# tumkibot1_relay_module.net
KiCad netlist of a schematic drawn in EasyEDA Pro
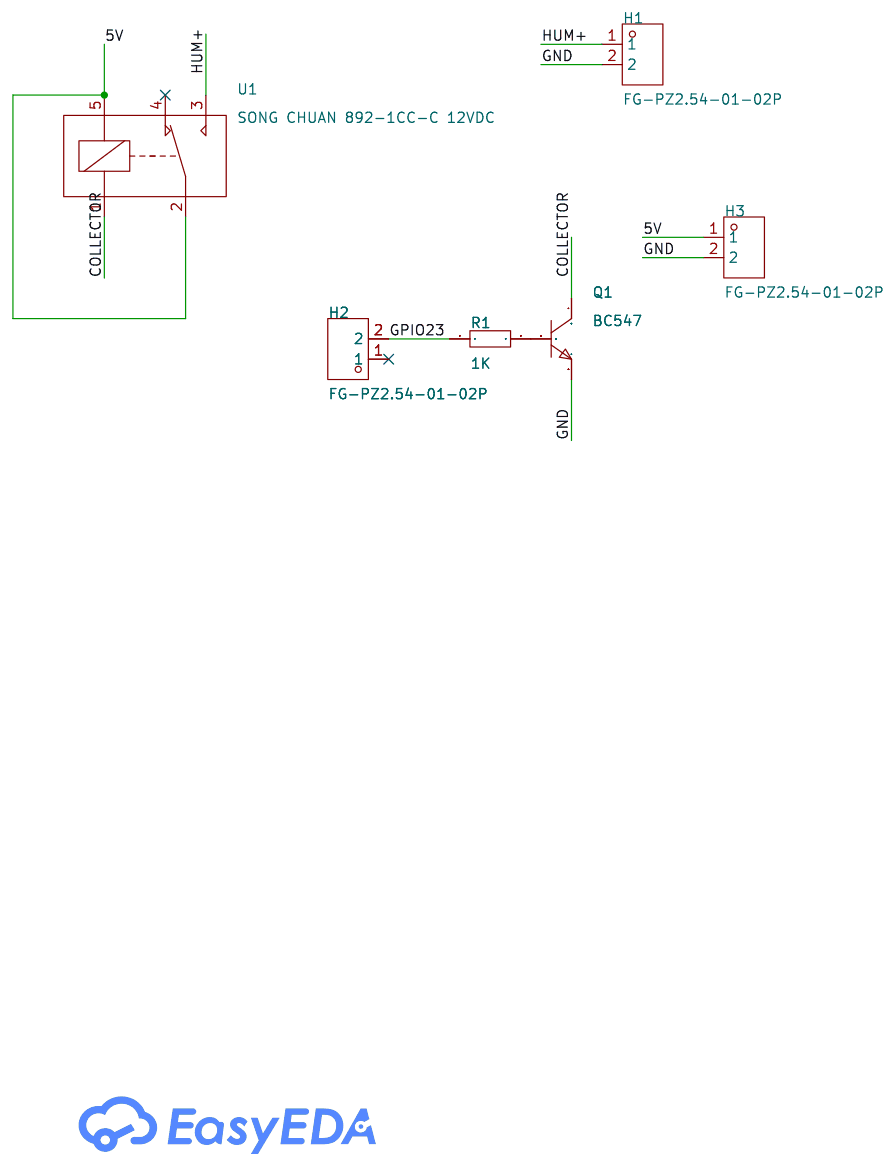
[diagram p0: schematic sheet]

(export (version "E")
  (design (tool "Eeschema 10.0.6"))
  (components
    (comp (ref "H1")
      (value "FG-PZ2.54-01-02P")
      (footprint "easyedapro:HDR-TH_2P-P2.54-V-M")
      (description "Pin Structure:1x2P Pitch:2.54mm Circluar Pins/Square Pins:Pin Header Number of Rows:1")
      (fields (field (name "Manufacturer") "FG(富港)"))
      (libsource (lib "easyedapro") (part "FG-PZ2.54-01-02P"))
    )
    (comp (ref "H2")
      (value "FG-PZ2.54-01-02P")
      (footprint "easyedapro:HDR-TH_2P-P2.54-V-M")
      (description "Pin Structure:1x2P Pitch:2.54mm Circluar Pins/Square Pins:Pin Header Number of Rows:1")
      (fields (field (name "Manufacturer") "FG(富港)"))
      (libsource (lib "easyedapro") (part "FG-PZ2.54-01-02P"))
    )
    (comp (ref "H3")
      (value "FG-PZ2.54-01-02P")
      (footprint "easyedapro:HDR-TH_2P-P2.54-V-M")
      (description "Pin Structure:1x2P Pitch:2.54mm Circluar Pins/Square Pins:Pin Header Number of Rows:1")
      (fields (field (name "Manufacturer") "FG(富港)"))
      (libsource (lib "easyedapro") (part "FG-PZ2.54-01-02P"))
    )
    (comp (ref "Q1")
      (value "BC547")
      (footprint "easyedapro:TO-92-3_L4.9-W3.7-P1.27-L")
      (fields (field (name "Manufacturer") "CJ(江苏长电/长晶)"))
      (libsource (lib "easyedapro") (part "BC547_C47089404"))
    )
    (comp (ref "R1") (value "10K") (footprint "easyedapro:R0603") (libsource (lib "easyedapro") (part "Res")))
    (comp (ref "U1")
      (value "SONG CHUAN 892-1CC-C 12VDC")
      (footprint "easyedapro:RELAY_SPDT_892-1CC-C")
      (libsource (lib "easyedapro") (part "SONG CHUAN 892-1CC-C 12VDC"))
    )
  )
  (nets
    (net (code "1") (name "/5V") (class "Default")
      (node (ref "H3") (pin "1") (pinfunction "1_1") (pintype "unspecified"))
      (node (ref "U1") (pin "2") (pintype "unspecified"))
      (node (ref "U1") (pin "5") (pintype "unspecified"))
    )
    (net (code "2") (name "/COLLECTOR") (class "Default")
      (node (ref "Q1") (pin "1") (pinfunction "C_1") (pintype "input"))
      (node (ref "U1") (pin "1") (pintype "unspecified"))
    )
    (net (code "3") (name "/GND") (class "Default")
      (node (ref "H1") (pin "2") (pinfunction "2_2") (pintype "unspecified"))
      (node (ref "H3") (pin "2") (pinfunction "2_2") (pintype "unspecified"))
      (node (ref "Q1") (pin "3") (pinfunction "E_3") (pintype "input"))
    )
    (net (code "4") (name "/GPIO23") (class "Default")
      (node (ref "H2") (pin "2") (pinfunction "2_2") (pintype "unspecified"))
      (node (ref "R1") (pin "1") (pinfunction "1_1") (pintype "input"))
    )
    (net (code "5") (name "/HUM+") (class "Default")
      (node (ref "H1") (pin "1") (pinfunction "1_1") (pintype "unspecified"))
      (node (ref "U1") (pin "3") (pintype "unspecified"))
    )
    (net (code "6") (name "Net-(Q1-B)") (class "Default")
      (node (ref "Q1") (pin "2") (pinfunction "B_2") (pintype "input"))
      (node (ref "R1") (pin "2") (pinfunction "2_2") (pintype "input"))
    )
    (net (code "7") (name "unconnected-(H2-Pad1)") (class "Default")
      (node (ref "H2") (pin "1") (pinfunction "1_1") (pintype "unspecified+no_connect"))
    )
    (net (code "8") (name "unconnected-(U1-Pad4)") (class "Default")
      (node (ref "U1") (pin "4") (pintype "unspecified+no_connect"))
    )
  )
)
